# x-IMU3-SA-Breakout.net
KiCad netlist of a schematic drawn in Altium Designer
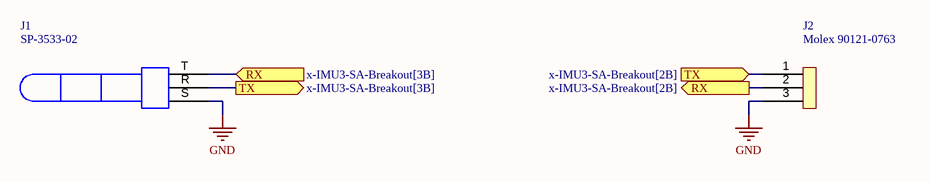
[diagram p0: x-IMU3-SA-Breakout.SchDoc]

(export (version "E")
  (design (tool "Eeschema 10.0.6"))
  (components
    (comp (ref "J1")
      (value "SP-3533-02")
      (footprint "SP-3533-02")
      (libsource (lib "x-io") (part "SP-3533-02"))
    )
    (comp (ref "J2")
      (value "Molex 90121-0763")
      (footprint "Molex 90121-0763")
      (libsource (lib "x-io") (part "Molex 90121-0763"))
    )
  )
  (nets
    (net (code "1") (name "/RX") (class "Default")
      (node (ref "J1") (pin "T") (pinfunction "T_T") (pintype "passive"))
      (node (ref "J2") (pin "2") (pinfunction "2_2") (pintype "passive"))
    )
    (net (code "2") (name "/TX") (class "Default")
      (node (ref "J1") (pin "R") (pinfunction "R_R") (pintype "passive"))
      (node (ref "J2") (pin "1") (pinfunction "1_1") (pintype "passive"))
    )
    (net (code "3") (name "GND") (class "Default")
      (node (ref "J1") (pin "S") (pinfunction "S_S") (pintype "passive"))
      (node (ref "J2") (pin "3") (pinfunction "3_3") (pintype "passive"))
    )
  )
)
